# opto-endstop_1_2.net
KiCad netlist of a schematic drawn in EAGLE
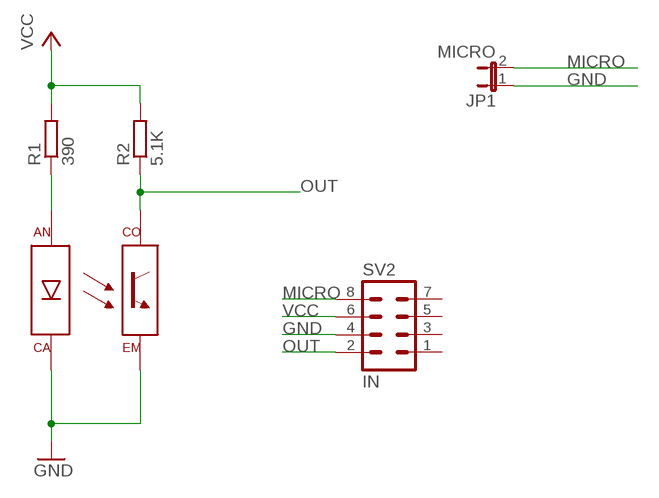
[diagram p0: schematic, sheet 1]

(export (version "E")
  (design (tool "Eeschema 10.0.6"))
  (components
    (comp (ref "JP1")
      (value "MICRO")
      (footprint "eagle-import:JP1")
      (libsource (lib "eagle-import") (part "JP1E"))
    )
    (comp (ref "R1")
      (value "390")
      (footprint "eagle-import:0204_5")
      (libsource (lib "eagle-import") (part "R-EU_0204/5"))
    )
    (comp (ref "R2")
      (value "5.1K")
      (footprint "eagle-import:0204_5")
      (libsource (lib "eagle-import") (part "R-EU_0204/5"))
    )
    (comp (ref "SV2")
      (value "IN")
      (footprint "eagle-import:MA04-2")
      (libsource (lib "eagle-import") (part "MA04-2"))
    )
    (comp (ref "U$1")
      (value "KTIR0521DS")
      (footprint "eagle-import:KTIR0521DS")
      (libsource (lib "eagle-import") (part "KTIR0521DS"))
    )
  )
  (nets
    (net (code "1") (name "/MICRO") (class "Default")
      (node (ref "JP1") (pin "2") (pinfunction "2_2") (pintype "passive"))
      (node (ref "SV2") (pin "8") (pinfunction "8_8") (pintype "passive"))
    )
    (net (code "2") (name "/OUT") (class "Default")
      (node (ref "R2") (pin "1") (pinfunction "1_1") (pintype "passive"))
      (node (ref "SV2") (pin "2") (pinfunction "2_2") (pintype "passive"))
      (node (ref "U$1") (pin "CO") (pinfunction "CO_CO") (pintype "passive"))
    )
    (net (code "3") (name "GND") (class "Default")
      (node (ref "JP1") (pin "1") (pinfunction "1_1") (pintype "passive"))
      (node (ref "SV2") (pin "4") (pinfunction "4_4") (pintype "passive"))
      (node (ref "U$1") (pin "CA") (pinfunction "CA_CA") (pintype "passive"))
      (node (ref "U$1") (pin "EM") (pinfunction "EM_EM") (pintype "passive"))
    )
    (net (code "4") (name "Net-(R1-Pad1)") (class "Default")
      (node (ref "R1") (pin "1") (pinfunction "1_1") (pintype "passive"))
      (node (ref "U$1") (pin "AN") (pinfunction "AN_AN") (pintype "passive"))
    )
    (net (code "5") (name "VCC") (class "Default")
      (node (ref "R1") (pin "2") (pinfunction "2_2") (pintype "passive"))
      (node (ref "R2") (pin "2") (pinfunction "2_2") (pintype "passive"))
      (node (ref "SV2") (pin "6") (pinfunction "6_6") (pintype "passive"))
    )
    (net (code "6") (name "unconnected-(SV2-Pad1)") (class "Default")
      (node (ref "SV2") (pin "1") (pinfunction "1_1") (pintype "passive"))
    )
    (net (code "7") (name "unconnected-(SV2-Pad3)") (class "Default")
      (node (ref "SV2") (pin "3") (pinfunction "3_3") (pintype "passive"))
    )
    (net (code "8") (name "unconnected-(SV2-Pad5)") (class "Default")
      (node (ref "SV2") (pin "5") (pinfunction "5_5") (pintype "passive"))
    )
    (net (code "9") (name "unconnected-(SV2-Pad7)") (class "Default")
      (node (ref "SV2") (pin "7") (pinfunction "7_7") (pintype "passive"))
    )
  )
)
